# Testadapter.net
KiCad netlist of a schematic drawn in EAGLE
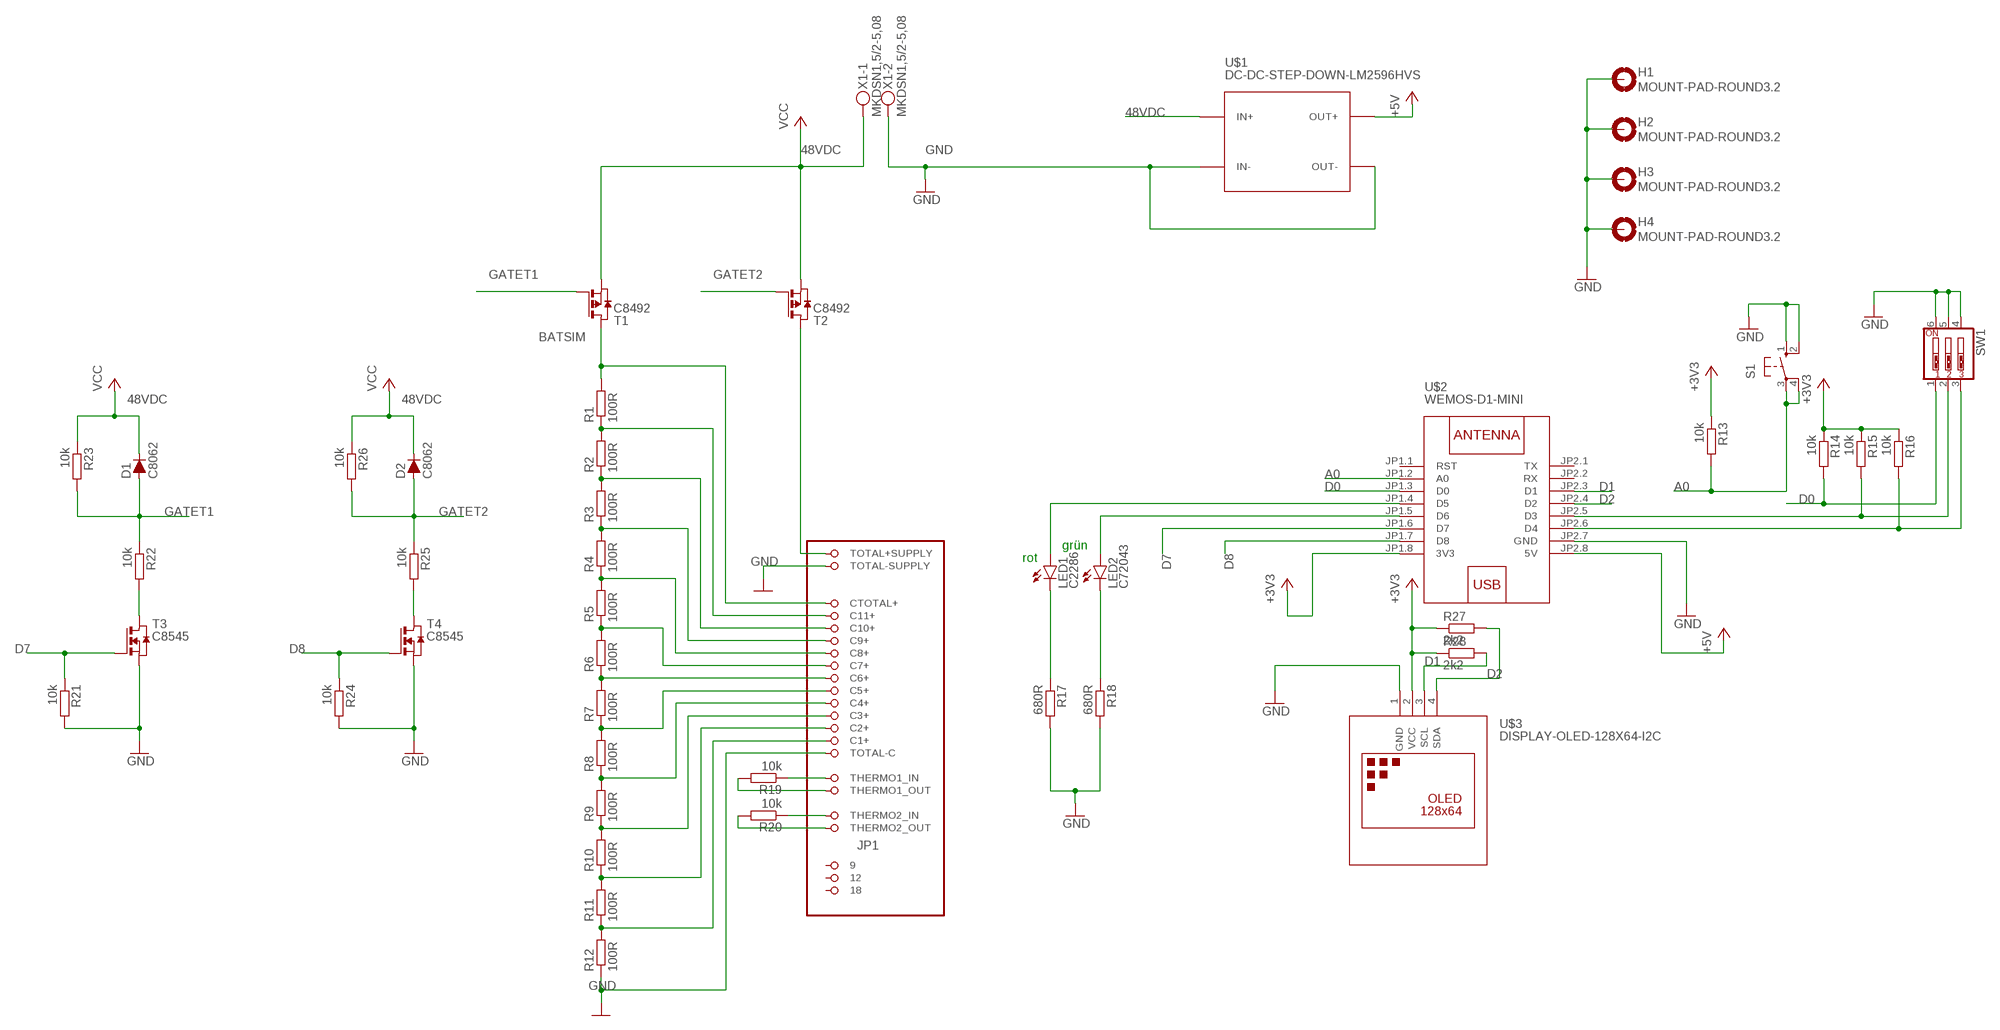
[diagram p0: schematic, sheet 1]

(export (version "E")
  (design (tool "Eeschema 10.0.6"))
  (components
    (comp (ref "D1")
      (value "C8062")
      (footprint "eagle-import:MELF-MLL34")
      (libsource (lib "eagle-import") (part "D-FILL-MLL-34"))
    )
    (comp (ref "D2")
      (value "C8062")
      (footprint "eagle-import:MELF-MLL34")
      (libsource (lib "eagle-import") (part "D-FILL-MLL-34"))
    )
    (comp (ref "H1")
      (value "MOUNT-PAD-ROUND3.2")
      (footprint "eagle-import:3,2-PAD")
      (libsource (lib "eagle-import") (part "MOUNT-PAD-ROUND3.2"))
    )
    (comp (ref "H2")
      (value "MOUNT-PAD-ROUND3.2")
      (footprint "eagle-import:3,2-PAD")
      (libsource (lib "eagle-import") (part "MOUNT-PAD-ROUND3.2"))
    )
    (comp (ref "H3")
      (value "MOUNT-PAD-ROUND3.2")
      (footprint "eagle-import:3,2-PAD")
      (libsource (lib "eagle-import") (part "MOUNT-PAD-ROUND3.2"))
    )
    (comp (ref "H4")
      (value "MOUNT-PAD-ROUND3.2")
      (footprint "eagle-import:3,2-PAD")
      (libsource (lib "eagle-import") (part "MOUNT-PAD-ROUND3.2"))
    )
    (comp (ref "JP1")
      (value "PINHD-2X11_MEB12S_MODULSEITE_SMD")
      (footprint "eagle-import:2X11_MEB12S_MODULSEITE_SMD")
      (libsource (lib "eagle-import") (part "PINHD-2X11_MEB12S_MODULSEITE_SMD"))
    )
    (comp (ref "LED1")
      (value "C2286")
      (footprint "eagle-import:CHIP-LED0603")
      (libsource (lib "eagle-import") (part "LEDCHIP-LED0603"))
    )
    (comp (ref "LED2")
      (value "C72043")
      (footprint "eagle-import:CHIP-LED0603")
      (libsource (lib "eagle-import") (part "LEDCHIP-LED0603"))
    )
    (comp (ref "R1")
      (value "100R")
      (footprint "eagle-import:R0805")
      (libsource (lib "eagle-import") (part "R-EU_R0805"))
    )
    (comp (ref "R2")
      (value "100R")
      (footprint "eagle-import:R0805")
      (libsource (lib "eagle-import") (part "R-EU_R0805"))
    )
    (comp (ref "R3")
      (value "100R")
      (footprint "eagle-import:R0805")
      (libsource (lib "eagle-import") (part "R-EU_R0805"))
    )
    (comp (ref "R4")
      (value "100R")
      (footprint "eagle-import:R0805")
      (libsource (lib "eagle-import") (part "R-EU_R0805"))
    )
    (comp (ref "R5")
      (value "100R")
      (footprint "eagle-import:R0805")
      (libsource (lib "eagle-import") (part "R-EU_R0805"))
    )
    (comp (ref "R6")
      (value "100R")
      (footprint "eagle-import:R0805")
      (libsource (lib "eagle-import") (part "R-EU_R0805"))
    )
    (comp (ref "R7")
      (value "100R")
      (footprint "eagle-import:R0805")
      (libsource (lib "eagle-import") (part "R-EU_R0805"))
    )
    (comp (ref "R8")
      (value "100R")
      (footprint "eagle-import:R0805")
      (libsource (lib "eagle-import") (part "R-EU_R0805"))
    )
    (comp (ref "R9")
      (value "100R")
      (footprint "eagle-import:R0805")
      (libsource (lib "eagle-import") (part "R-EU_R0805"))
    )
    (comp (ref "R10")
      (value "100R")
      (footprint "eagle-import:R0805")
      (libsource (lib "eagle-import") (part "R-EU_R0805"))
    )
    (comp (ref "R11")
      (value "100R")
      (footprint "eagle-import:R0805")
      (libsource (lib "eagle-import") (part "R-EU_R0805"))
    )
    (comp (ref "R12")
      (value "100R")
      (footprint "eagle-import:R0805")
      (libsource (lib "eagle-import") (part "R-EU_R0805"))
    )
    (comp (ref "R13")
      (value "10k")
      (footprint "eagle-import:R0805")
      (libsource (lib "eagle-import") (part "R-EU_R0805"))
    )
    (comp (ref "R14")
      (value "10k")
      (footprint "eagle-import:R0805")
      (libsource (lib "eagle-import") (part "R-EU_R0805"))
    )
    (comp (ref "R15")
      (value "10k")
      (footprint "eagle-import:R0805")
      (libsource (lib "eagle-import") (part "R-EU_R0805"))
    )
    (comp (ref "R16")
      (value "10k")
      (footprint "eagle-import:R0805")
      (libsource (lib "eagle-import") (part "R-EU_R0805"))
    )
    (comp (ref "R17")
      (value "680R")
      (footprint "eagle-import:R0805")
      (libsource (lib "eagle-import") (part "R-EU_R0805"))
    )
    (comp (ref "R18")
      (value "680R")
      (footprint "eagle-import:R0805")
      (libsource (lib "eagle-import") (part "R-EU_R0805"))
    )
    (comp (ref "R19")
      (value "10k")
      (footprint "eagle-import:R0805")
      (libsource (lib "eagle-import") (part "R-EU_R0805"))
    )
    (comp (ref "R20")
      (value "10k")
      (footprint "eagle-import:R0805")
      (libsource (lib "eagle-import") (part "R-EU_R0805"))
    )
    (comp (ref "R21")
      (value "10k")
      (footprint "eagle-import:R0805")
      (libsource (lib "eagle-import") (part "R-EU_R0805"))
    )
    (comp (ref "R22")
      (value "10k")
      (footprint "eagle-import:R0805")
      (libsource (lib "eagle-import") (part "R-EU_R0805"))
    )
    (comp (ref "R23")
      (value "10k")
      (footprint "eagle-import:R0805")
      (libsource (lib "eagle-import") (part "R-EU_R0805"))
    )
    (comp (ref "R24")
      (value "10k")
      (footprint "eagle-import:R0805")
      (libsource (lib "eagle-import") (part "R-EU_R0805"))
    )
    (comp (ref "R25")
      (value "10k")
      (footprint "eagle-import:R0805")
      (libsource (lib "eagle-import") (part "R-EU_R0805"))
    )
    (comp (ref "R26")
      (value "10k")
      (footprint "eagle-import:R0805")
      (libsource (lib "eagle-import") (part "R-EU_R0805"))
    )
    (comp (ref "R27")
      (value "2k2")
      (footprint "eagle-import:R0805")
      (libsource (lib "eagle-import") (part "R-EU_R0805"))
    )
    (comp (ref "R28")
      (value "2k2")
      (footprint "eagle-import:R0805")
      (libsource (lib "eagle-import") (part "R-EU_R0805"))
    )
    (comp (ref "S1")
      (value "10-XX")
      (footprint "eagle-import:B3F-10XX")
      (fields (field (name "MPN") "B3F-1000"))
      (libsource (lib "eagle-import") (part "10-XX"))
    )
    (comp (ref "SW1")
      (value "SW_DIP-3")
      (footprint "eagle-import:EDG-03")
      (libsource (lib "eagle-import") (part "SW_DIP-3"))
    )
    (comp (ref "T1")
      (value "C8492")
      (footprint "eagle-import:SOT-23")
      (libsource (lib "eagle-import") (part "PMOSSOT23"))
    )
    (comp (ref "T2")
      (value "C8492")
      (footprint "eagle-import:SOT-23")
      (libsource (lib "eagle-import") (part "PMOSSOT23"))
    )
    (comp (ref "T3")
      (value "C8545")
      (footprint "eagle-import:SOT-23")
      (libsource (lib "eagle-import") (part "NMOSSOT23"))
    )
    (comp (ref "T4")
      (value "C8545")
      (footprint "eagle-import:SOT-23")
      (libsource (lib "eagle-import") (part "NMOSSOT23"))
    )
    (comp (ref "U$1")
      (value "DC-DC-STEP-DOWN-LM2596HVS")
      (footprint "eagle-import:DC-DC-STEP-DOWN-LM2596HVS")
      (libsource (lib "eagle-import") (part "DC-DC-STEP-DOWN-LM2596HVS"))
    )
    (comp (ref "U$2")
      (value "WEMOS-D1-MINI")
      (footprint "eagle-import:WEMOS-D1-MINI")
      (libsource (lib "eagle-import") (part "WEMOS-D1-MINI"))
    )
    (comp (ref "U$3")
      (value "DISPLAY-OLED-128X64-I2C")
      (footprint "eagle-import:DISPLAY-OLED-128X64-I2C")
      (libsource (lib "eagle-import") (part "DISPLAY-OLED-128X64-I2C"))
    )
    (comp (ref "X1")
      (value "MKDSN1,5/2-5,08")
      (footprint "eagle-import:MKDSN1,5_2-5,08")
      (libsource (lib "eagle-import") (part "MKDSN1,5/2-5,08"))
    )
  )
  (nets
    (net (code "1") (name "+3V3") (class "Default")
      (node (ref "R13") (pin "1") (pinfunction "1_1") (pintype "passive"))
      (node (ref "R14") (pin "1") (pinfunction "1_1") (pintype "passive"))
      (node (ref "R15") (pin "1") (pinfunction "1_1") (pintype "passive"))
      (node (ref "R16") (pin "1") (pinfunction "1_1") (pintype "passive"))
      (node (ref "R27") (pin "1") (pinfunction "1_1") (pintype "passive"))
      (node (ref "R28") (pin "1") (pinfunction "1_1") (pintype "passive"))
      (node (ref "U$2") (pin "JP1.8") (pinfunction "3V3_JP1.8") (pintype "power_in"))
      (node (ref "U$3") (pin "2") (pinfunction "VCC_2") (pintype "power_in"))
    )
    (net (code "2") (name "+5V") (class "Default")
      (node (ref "U$1") (pin "OUT+") (pinfunction "OUT+_OUT+") (pintype "bidirectional"))
      (node (ref "U$2") (pin "JP2.8") (pinfunction "5V_JP2.8") (pintype "power_in"))
    )
    (net (code "3") (name "/A0") (class "Default")
      (node (ref "R13") (pin "2") (pinfunction "2_2") (pintype "passive"))
      (node (ref "S1") (pin "3") (pinfunction "P_3") (pintype "passive"))
      (node (ref "S1") (pin "4") (pinfunction "P1_4") (pintype "passive"))
      (node (ref "U$2") (pin "JP1.2") (pinfunction "A0_JP1.2") (pintype "bidirectional"))
    )
    (net (code "4") (name "/BATSIM") (class "Default")
      (node (ref "JP1") (pin "21") (pinfunction "CTOTAL+_21") (pintype "passive"))
      (node (ref "R1") (pin "2") (pinfunction "2_2") (pintype "passive"))
      (node (ref "T1") (pin "1") (pinfunction "D_1") (pintype "passive"))
    )
    (net (code "5") (name "/D0") (class "Default")
      (node (ref "R14") (pin "2") (pinfunction "2_2") (pintype "passive"))
      (node (ref "SW1") (pin "1") (pinfunction "1_1") (pintype "passive"))
      (node (ref "U$2") (pin "JP1.3") (pinfunction "D0_JP1.3") (pintype "bidirectional"))
    )
    (net (code "6") (name "/D1") (class "Default")
      (node (ref "R28") (pin "2") (pinfunction "2_2") (pintype "passive"))
      (node (ref "U$2") (pin "JP2.3") (pinfunction "D1_JP2.3") (pintype "bidirectional"))
      (node (ref "U$3") (pin "3") (pinfunction "SCL_3") (pintype "bidirectional"))
    )
    (net (code "7") (name "/D2") (class "Default")
      (node (ref "R27") (pin "2") (pinfunction "2_2") (pintype "passive"))
      (node (ref "U$2") (pin "JP2.4") (pinfunction "D2_JP2.4") (pintype "bidirectional"))
      (node (ref "U$3") (pin "4") (pinfunction "SDA_4") (pintype "bidirectional"))
    )
    (net (code "8") (name "/D7") (class "Default")
      (node (ref "R21") (pin "1") (pinfunction "1_1") (pintype "passive"))
      (node (ref "T3") (pin "3") (pinfunction "G_3") (pintype "passive"))
      (node (ref "U$2") (pin "JP1.6") (pinfunction "D7_JP1.6") (pintype "bidirectional"))
    )
    (net (code "9") (name "/D8") (class "Default")
      (node (ref "R24") (pin "1") (pinfunction "1_1") (pintype "passive"))
      (node (ref "T4") (pin "3") (pinfunction "G_3") (pintype "passive"))
      (node (ref "U$2") (pin "JP1.7") (pinfunction "D8_JP1.7") (pintype "bidirectional"))
    )
    (net (code "10") (name "/GATET1") (class "Default")
      (node (ref "D1") (pin "2") (pinfunction "A_2") (pintype "passive"))
      (node (ref "R22") (pin "1") (pinfunction "1_1") (pintype "passive"))
      (node (ref "R23") (pin "2") (pinfunction "2_2") (pintype "passive"))
      (node (ref "T1") (pin "3") (pinfunction "G_3") (pintype "passive"))
    )
    (net (code "11") (name "/GATET2") (class "Default")
      (node (ref "D2") (pin "2") (pinfunction "A_2") (pintype "passive"))
      (node (ref "R25") (pin "1") (pinfunction "1_1") (pintype "passive"))
      (node (ref "R26") (pin "2") (pinfunction "2_2") (pintype "passive"))
      (node (ref "T2") (pin "3") (pinfunction "G_3") (pintype "passive"))
    )
    (net (code "12") (name "GND") (class "Default")
      (node (ref "H1") (pin "B3,2") (pinfunction "MOUNT_B3,2") (pintype "passive"))
      (node (ref "H2") (pin "B3,2") (pinfunction "MOUNT_B3,2") (pintype "passive"))
      (node (ref "H3") (pin "B3,2") (pinfunction "MOUNT_B3,2") (pintype "passive"))
      (node (ref "H4") (pin "B3,2") (pinfunction "MOUNT_B3,2") (pintype "passive"))
      (node (ref "JP1") (pin "7") (pinfunction "TOTAL-SUPPLY_7") (pintype "passive"))
      (node (ref "JP1") (pin "9") (pinfunction "TOTAL-C_9") (pintype "passive"))
      (node (ref "R12") (pin "1") (pinfunction "1_1") (pintype "passive"))
      (node (ref "R17") (pin "2") (pinfunction "2_2") (pintype "passive"))
      (node (ref "R18") (pin "2") (pinfunction "2_2") (pintype "passive"))
      (node (ref "R21") (pin "2") (pinfunction "2_2") (pintype "passive"))
      (node (ref "R24") (pin "2") (pinfunction "2_2") (pintype "passive"))
      (node (ref "S1") (pin "1") (pinfunction "S_1") (pintype "passive"))
      (node (ref "S1") (pin "2") (pinfunction "S1_2") (pintype "passive"))
      (node (ref "SW1") (pin "4") (pinfunction "4_4") (pintype "passive"))
      (node (ref "SW1") (pin "5") (pinfunction "5_5") (pintype "passive"))
      (node (ref "SW1") (pin "6") (pinfunction "6_6") (pintype "passive"))
      (node (ref "T3") (pin "2") (pinfunction "S_2") (pintype "passive"))
      (node (ref "T4") (pin "2") (pinfunction "S_2") (pintype "passive"))
      (node (ref "U$1") (pin "IN-") (pinfunction "IN-_IN-") (pintype "bidirectional"))
      (node (ref "U$1") (pin "OUT-") (pinfunction "OUT-_OUT-") (pintype "bidirectional"))
      (node (ref "U$2") (pin "JP2.7") (pinfunction "GND_JP2.7") (pintype "power_in"))
      (node (ref "U$3") (pin "1") (pinfunction "GND_1") (pintype "power_in"))
      (node (ref "X1") (pin "2") (pinfunction "KL_2") (pintype "passive"))
    )
    (net (code "13") (name "Net-(JP1-C1+)") (class "Default")
      (node (ref "JP1") (pin "10") (pinfunction "C1+_10") (pintype "passive"))
      (node (ref "R11") (pin "1") (pinfunction "1_1") (pintype "passive"))
      (node (ref "R12") (pin "2") (pinfunction "2_2") (pintype "passive"))
    )
    (net (code "14") (name "Net-(JP1-C2+)") (class "Default")
      (node (ref "JP1") (pin "11") (pinfunction "C2+_11") (pintype "passive"))
      (node (ref "R10") (pin "1") (pinfunction "1_1") (pintype "passive"))
      (node (ref "R11") (pin "2") (pinfunction "2_2") (pintype "passive"))
    )
    (net (code "15") (name "Net-(JP1-C3+)") (class "Default")
      (node (ref "JP1") (pin "12") (pinfunction "C3+_12") (pintype "passive"))
      (node (ref "R10") (pin "2") (pinfunction "2_2") (pintype "passive"))
      (node (ref "R9") (pin "1") (pinfunction "1_1") (pintype "passive"))
    )
    (net (code "16") (name "Net-(JP1-C4+)") (class "Default")
      (node (ref "JP1") (pin "13") (pinfunction "C4+_13") (pintype "passive"))
      (node (ref "R8") (pin "1") (pinfunction "1_1") (pintype "passive"))
      (node (ref "R9") (pin "2") (pinfunction "2_2") (pintype "passive"))
    )
    (net (code "17") (name "Net-(JP1-C5+)") (class "Default")
      (node (ref "JP1") (pin "14") (pinfunction "C5+_14") (pintype "passive"))
      (node (ref "R7") (pin "1") (pinfunction "1_1") (pintype "passive"))
      (node (ref "R8") (pin "2") (pinfunction "2_2") (pintype "passive"))
    )
    (net (code "18") (name "Net-(JP1-C6+)") (class "Default")
      (node (ref "JP1") (pin "15") (pinfunction "C6+_15") (pintype "passive"))
      (node (ref "R6") (pin "1") (pinfunction "1_1") (pintype "passive"))
      (node (ref "R7") (pin "2") (pinfunction "2_2") (pintype "passive"))
    )
    (net (code "19") (name "Net-(JP1-C7+)") (class "Default")
      (node (ref "JP1") (pin "16") (pinfunction "C7+_16") (pintype "passive"))
      (node (ref "R5") (pin "1") (pinfunction "1_1") (pintype "passive"))
      (node (ref "R6") (pin "2") (pinfunction "2_2") (pintype "passive"))
    )
    (net (code "20") (name "Net-(JP1-C8+)") (class "Default")
      (node (ref "JP1") (pin "17") (pinfunction "C8+_17") (pintype "passive"))
      (node (ref "R4") (pin "1") (pinfunction "1_1") (pintype "passive"))
      (node (ref "R5") (pin "2") (pinfunction "2_2") (pintype "passive"))
    )
    (net (code "21") (name "Net-(JP1-C9+)") (class "Default")
      (node (ref "JP1") (pin "18") (pinfunction "C9+_18") (pintype "passive"))
      (node (ref "R3") (pin "1") (pinfunction "1_1") (pintype "passive"))
      (node (ref "R4") (pin "2") (pinfunction "2_2") (pintype "passive"))
    )
    (net (code "22") (name "Net-(JP1-C10+)") (class "Default")
      (node (ref "JP1") (pin "19") (pinfunction "C10+_19") (pintype "passive"))
      (node (ref "R2") (pin "1") (pinfunction "1_1") (pintype "passive"))
      (node (ref "R3") (pin "2") (pinfunction "2_2") (pintype "passive"))
    )
    (net (code "23") (name "Net-(JP1-C11+)") (class "Default")
      (node (ref "JP1") (pin "20") (pinfunction "C11+_20") (pintype "passive"))
      (node (ref "R1") (pin "1") (pinfunction "1_1") (pintype "passive"))
      (node (ref "R2") (pin "2") (pinfunction "2_2") (pintype "passive"))
    )
    (net (code "24") (name "Net-(JP1-THERMO1_IN)") (class "Default")
      (node (ref "JP1") (pin "1") (pinfunction "THERMO1_IN_1") (pintype "passive"))
      (node (ref "R19") (pin "1") (pinfunction "1_1") (pintype "passive"))
    )
    (net (code "25") (name "Net-(JP1-THERMO1_OUT)") (class "Default")
      (node (ref "JP1") (pin "3") (pinfunction "THERMO1_OUT_3") (pintype "passive"))
      (node (ref "R19") (pin "2") (pinfunction "2_2") (pintype "passive"))
    )
    (net (code "26") (name "Net-(JP1-THERMO2_IN)") (class "Default")
      (node (ref "JP1") (pin "2") (pinfunction "THERMO2_IN_2") (pintype "passive"))
      (node (ref "R20") (pin "1") (pinfunction "1_1") (pintype "passive"))
    )
    (net (code "27") (name "Net-(JP1-THERMO2_OUT)") (class "Default")
      (node (ref "JP1") (pin "4") (pinfunction "THERMO2_OUT_4") (pintype "passive"))
      (node (ref "R20") (pin "2") (pinfunction "2_2") (pintype "passive"))
    )
    (net (code "28") (name "Net-(JP1-TOTAL+SUPPLY)") (class "Default")
      (node (ref "JP1") (pin "22") (pinfunction "TOTAL+SUPPLY_22") (pintype "passive"))
      (node (ref "T2") (pin "1") (pinfunction "D_1") (pintype "passive"))
    )
    (net (code "29") (name "Net-(LED1-PadC)") (class "Default")
      (node (ref "LED1") (pin "C") (pinfunction "C_C") (pintype "passive"))
      (node (ref "R17") (pin "1") (pinfunction "1_1") (pintype "passive"))
    )
    (net (code "30") (name "Net-(LED2-PadC)") (class "Default")
      (node (ref "LED2") (pin "C") (pinfunction "C_C") (pintype "passive"))
      (node (ref "R18") (pin "1") (pinfunction "1_1") (pintype "passive"))
    )
    (net (code "31") (name "Net-(T3-D)") (class "Default")
      (node (ref "R22") (pin "2") (pinfunction "2_2") (pintype "passive"))
      (node (ref "T3") (pin "1") (pinfunction "D_1") (pintype "passive"))
    )
    (net (code "32") (name "Net-(T4-D)") (class "Default")
      (node (ref "R25") (pin "2") (pinfunction "2_2") (pintype "passive"))
      (node (ref "T4") (pin "1") (pinfunction "D_1") (pintype "passive"))
    )
    (net (code "33") (name "Net-(U$2-D3)") (class "Default")
      (node (ref "R15") (pin "2") (pinfunction "2_2") (pintype "passive"))
      (node (ref "SW1") (pin "2") (pinfunction "2_2") (pintype "passive"))
      (node (ref "U$2") (pin "JP2.5") (pinfunction "D3_JP2.5") (pintype "bidirectional"))
    )
    (net (code "34") (name "Net-(U$2-D4)") (class "Default")
      (node (ref "R16") (pin "2") (pinfunction "2_2") (pintype "passive"))
      (node (ref "SW1") (pin "3") (pinfunction "3_3") (pintype "passive"))
      (node (ref "U$2") (pin "JP2.6") (pinfunction "D4_JP2.6") (pintype "bidirectional"))
    )
    (net (code "35") (name "Net-(U$2-D5)") (class "Default")
      (node (ref "LED1") (pin "A") (pinfunction "A_A") (pintype "passive"))
      (node (ref "U$2") (pin "JP1.4") (pinfunction "D5_JP1.4") (pintype "bidirectional"))
    )
    (net (code "36") (name "Net-(U$2-D6)") (class "Default")
      (node (ref "LED2") (pin "A") (pinfunction "A_A") (pintype "passive"))
      (node (ref "U$2") (pin "JP1.5") (pinfunction "D6_JP1.5") (pintype "bidirectional"))
    )
    (net (code "37") (name "VCC") (class "Default")
      (node (ref "D1") (pin "1") (pinfunction "C_1") (pintype "passive"))
      (node (ref "D2") (pin "1") (pinfunction "C_1") (pintype "passive"))
      (node (ref "R23") (pin "1") (pinfunction "1_1") (pintype "passive"))
      (node (ref "R26") (pin "1") (pinfunction "1_1") (pintype "passive"))
      (node (ref "T1") (pin "2") (pinfunction "S_2") (pintype "passive"))
      (node (ref "T2") (pin "2") (pinfunction "S_2") (pintype "passive"))
      (node (ref "U$1") (pin "IN+") (pinfunction "IN+_IN+") (pintype "bidirectional"))
      (node (ref "X1") (pin "1") (pinfunction "KL_1") (pintype "passive"))
    )
    (net (code "38") (name "unconnected-(JP1-9-Pad5)") (class "Default")
      (node (ref "JP1") (pin "5") (pinfunction "9_5") (pintype "passive"))
    )
    (net (code "39") (name "unconnected-(JP1-12-Pad6)") (class "Default")
      (node (ref "JP1") (pin "6") (pinfunction "12_6") (pintype "passive"))
    )
    (net (code "40") (name "unconnected-(JP1-18-Pad8)") (class "Default")
      (node (ref "JP1") (pin "8") (pinfunction "18_8") (pintype "passive"))
    )
    (net (code "41") (name "unconnected-(U$2-RST-PadJP1.1)") (class "Default")
      (node (ref "U$2") (pin "JP1.1") (pinfunction "RST_JP1.1") (pintype "bidirectional"))
    )
    (net (code "42") (name "unconnected-(U$2-RX-PadJP2.2)") (class "Default")
      (node (ref "U$2") (pin "JP2.2") (pinfunction "RX_JP2.2") (pintype "bidirectional"))
    )
    (net (code "43") (name "unconnected-(U$2-TX-PadJP2.1)") (class "Default")
      (node (ref "U$2") (pin "JP2.1") (pinfunction "TX_JP2.1") (pintype "bidirectional"))
    )
  )
)
